# dht_bme280.net
KiCad netlist of a schematic drawn in Altium Designer
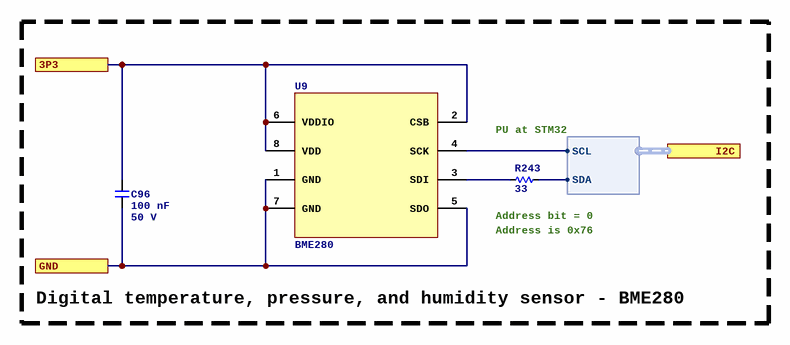
[diagram p0: dht_bme280.SchDoc]

(export (version "E")
  (design (tool "Eeschema 10.0.6"))
  (components
    (comp (ref "C96")
      (value "CL05B104KB54PNC")
      (footprint "C0402")
      (fields
        (field (name "CAPACITANCE") "100 nF")
        (field (name "MANUFACTURER") "Samsung Electro-Mechanics")
        (field (name "VOLTAGE RATING") "50 V")
      )
      (libsource (lib "database") (part "__template_cap"))
    )
    (comp (ref "R243")
      (value "33")
      (footprint "R0402")
      (fields
        (field (name "TOLERANCE") "1%")
        (field (name "MANUFACTURER PART NUMBER") "0402WGF330JTCE")
        (field (name "MANUFACTURER") "UNI-ROYAL(Uniroyal Elec)")
      )
      (libsource (lib "database") (part "__template_resistor"))
    )
    (comp (ref "U9")
      (value "BME280")
      (footprint "BOSCH_BME280")
      (description "Pressure, Temperature and Humidity Sensor Digital Output 1.8V 8-Pin LGA T/R")
      (fields (field (name "MANUFACTURER") "Bosch Tools"))
      (libsource (lib "database") (part "BME280"))
    )
  )
  (nets
    (net (code "2") (name "/3P3") (class "Default")
      (node (ref "C96") (pin "1") (pintype "passive"))
      (node (ref "U9") (pin "2") (pinfunction "CSB_2") (pintype "passive"))
      (node (ref "U9") (pin "6") (pinfunction "VDDIO_6") (pintype "passive"))
      (node (ref "U9") (pin "8") (pinfunction "VDD_8") (pintype "passive"))
    )
    (net (code "3") (name "/GND") (class "Default")
      (node (ref "C96") (pin "2") (pintype "passive"))
      (node (ref "U9") (pin "1") (pinfunction "GND_1") (pintype "passive"))
      (node (ref "U9") (pin "5") (pinfunction "SDO_5") (pintype "passive"))
      (node (ref "U9") (pin "7") (pinfunction "GND_7") (pintype "passive"))
    )
    (net (code "4") (name "/SCL") (class "Default")
      (node (ref "U9") (pin "4") (pinfunction "SCK_4") (pintype "passive"))
    )
    (net (code "5") (name "/SDA") (class "Default") (node (ref "R243") (pin "1") (pintype "passive")))
    (net (code "7") (name "Net-(U9-SDI)") (class "Default")
      (node (ref "R243") (pin "2") (pintype "passive"))
      (node (ref "U9") (pin "3") (pinfunction "SDI_3") (pintype "passive"))
    )
  )
)
